# SCH_New-Project_2025-06-10_1.net
KiCad netlist of a schematic drawn in EasyEDA
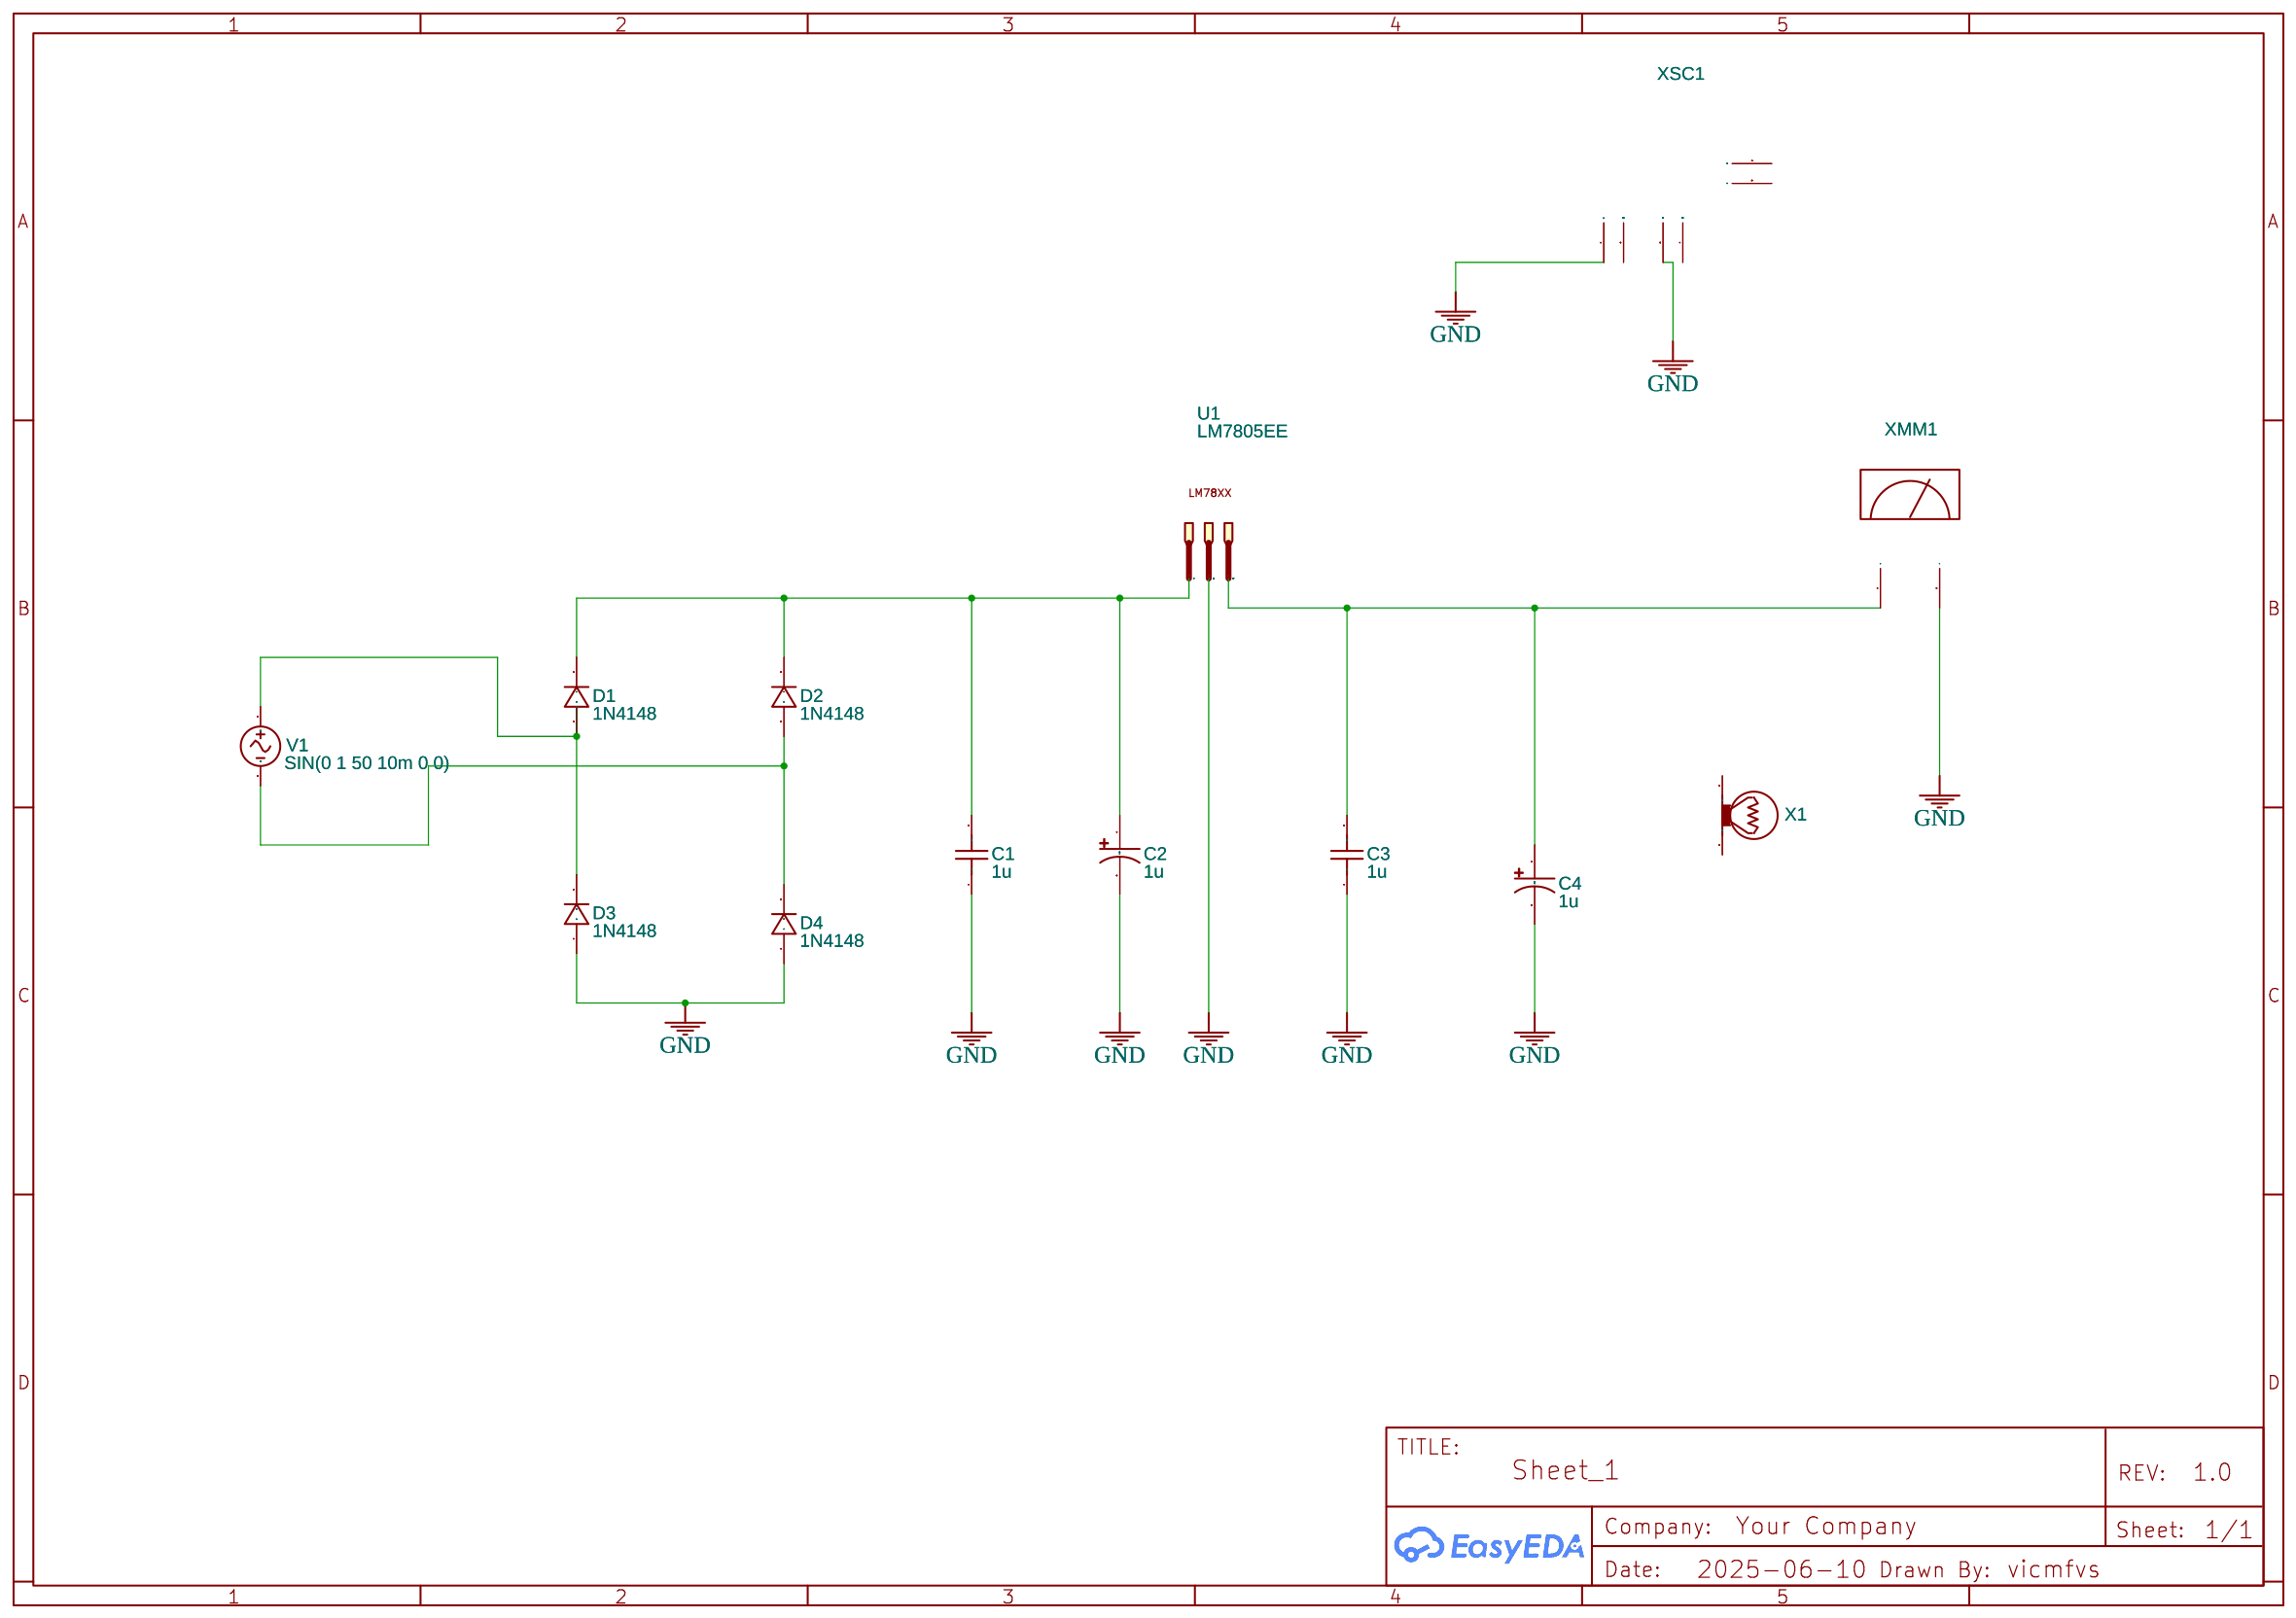
[diagram p0: schematic sheet]

(export (version "E")
  (design (tool "Eeschema 10.0.6"))
  (components
    (comp (ref "C1") (value "1u") (libsource (lib "") (part "Capacitor_US")))
    (comp (ref "C2") (value "1u") (libsource (lib "") (part "Capacitor_Electrolytic_US")))
    (comp (ref "C3") (value "1u") (libsource (lib "") (part "Capacitor_US")))
    (comp (ref "C4") (value "1u") (libsource (lib "") (part "Capacitor_Electrolytic_US")))
    (comp (ref "D1") (value "1N4148") (libsource (lib "") (part "1N4148")))
    (comp (ref "D2") (value "1N4148") (libsource (lib "") (part "1N4148")))
    (comp (ref "D3") (value "1N4148") (libsource (lib "") (part "1N4148")))
    (comp (ref "D4") (value "1N4148") (libsource (lib "") (part "1N4148")))
    (comp (ref "U1") (value "LM7805EE") (libsource (lib "") (part "78XX")))
    (comp (ref "V1") (value "SIN(0 1 50 10m 0 0)") (libsource (lib "") (part "VSin")))
    (comp (ref "X1") (value "Lamp") (libsource (lib "") (part "LAMP")))
    (comp (ref "XMM1") (value "Multimeter") (libsource (lib "") (part "MULTIMETER")))
    (comp (ref "XSC1") (value "Oscilloscope") (libsource (lib "") (part "OSCILLOSCOPE")))
  )
  (nets
    (net (code "1") (name "GND") (class "Default")
      (node (ref "C1") (pin "1") (pinfunction "1_1") (pintype "unspecified"))
      (node (ref "C2") (pin "2") (pinfunction "2_2") (pintype "unspecified"))
      (node (ref "C3") (pin "1") (pinfunction "1_1") (pintype "unspecified"))
      (node (ref "C4") (pin "2") (pinfunction "2_2") (pintype "unspecified"))
      (node (ref "D3") (pin "1") (pinfunction "A_1") (pintype "unspecified"))
      (node (ref "D4") (pin "1") (pinfunction "A_1") (pintype "unspecified"))
      (node (ref "U1") (pin "2") (pinfunction "GND_2") (pintype "unspecified"))
      (node (ref "XMM1") (pin "2") (pinfunction "I_2") (pintype "unspecified"))
      (node (ref "XSC1") (pin "1") (pinfunction "A_1") (pintype "unspecified"))
      (node (ref "XSC1") (pin "3") (pinfunction "B_3") (pintype "unspecified"))
    )
    (net (code "2") (name "Net-(D1-A)") (class "Default")
      (node (ref "D1") (pin "1") (pinfunction "A_1") (pintype "unspecified"))
      (node (ref "D3") (pin "2") (pinfunction "K_2") (pintype "unspecified"))
      (node (ref "V1") (pin "1") (pinfunction "1_1") (pintype "unspecified"))
    )
    (net (code "3") (name "Net-(D1-K)") (class "Default")
      (node (ref "C1") (pin "2") (pinfunction "2_2") (pintype "unspecified"))
      (node (ref "C2") (pin "1") (pinfunction "1_1") (pintype "unspecified"))
      (node (ref "D1") (pin "2") (pinfunction "K_2") (pintype "unspecified"))
      (node (ref "D2") (pin "2") (pinfunction "K_2") (pintype "unspecified"))
      (node (ref "U1") (pin "1") (pinfunction "IN_1") (pintype "unspecified"))
    )
    (net (code "4") (name "Net-(D2-A)") (class "Default")
      (node (ref "D2") (pin "1") (pinfunction "A_1") (pintype "unspecified"))
      (node (ref "D4") (pin "2") (pinfunction "K_2") (pintype "unspecified"))
      (node (ref "V1") (pin "2") (pinfunction "2_2") (pintype "unspecified"))
    )
    (net (code "5") (name "Net-(U1-OUT)") (class "Default")
      (node (ref "C3") (pin "2") (pinfunction "2_2") (pintype "unspecified"))
      (node (ref "C4") (pin "1") (pinfunction "1_1") (pintype "unspecified"))
      (node (ref "U1") (pin "3") (pinfunction "OUT_3") (pintype "unspecified"))
      (node (ref "XMM1") (pin "1") (pinfunction "+_1") (pintype "unspecified"))
    )
    (net (code "6") (name "unconnected-(X1-Pad1)") (class "Default")
      (node (ref "X1") (pin "1") (pinfunction "1_1") (pintype "unspecified"))
    )
    (net (code "7") (name "unconnected-(X1-Pad2)") (class "Default")
      (node (ref "X1") (pin "2") (pinfunction "2_2") (pintype "unspecified"))
    )
    (net (code "8") (name "unconnected-(XSC1-GND1-Pad2)") (class "Default")
      (node (ref "XSC1") (pin "2") (pinfunction "GND1_2") (pintype "unspecified"))
    )
    (net (code "9") (name "unconnected-(XSC1-GND2-Pad4)") (class "Default")
      (node (ref "XSC1") (pin "4") (pinfunction "GND2_4") (pintype "unspecified"))
    )
    (net (code "10") (name "unconnected-(XSC1-T+-Pad5)") (class "Default")
      (node (ref "XSC1") (pin "5") (pinfunction "T+_5") (pintype "unspecified"))
    )
    (net (code "11") (name "unconnected-(XSC1-T--Pad6)") (class "Default")
      (node (ref "XSC1") (pin "6") (pinfunction "T-_6") (pintype "unspecified"))
    )
  )
)
